# Analog_Input.net
KiCad netlist of a schematic drawn in Altium Designer
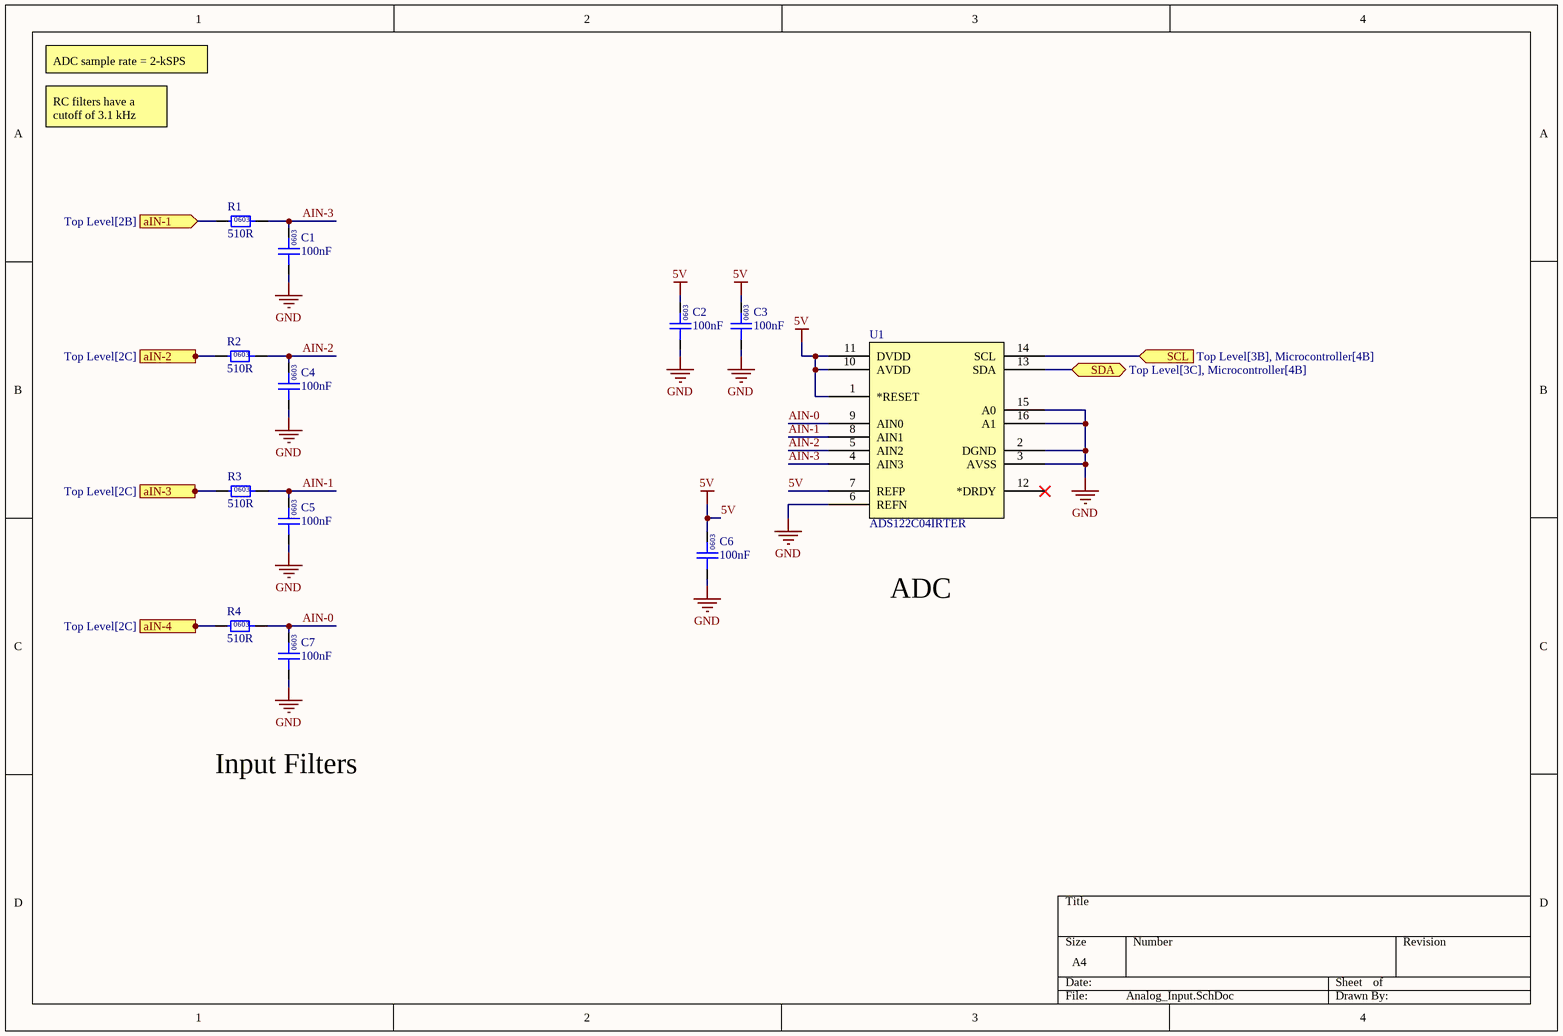
[diagram p0: Analog_Input.SchDoc]

(export (version "E")
  (design (tool "Eeschema 10.0.6"))
  (components
    (comp (ref "C1")
      (value "100nF")
      (footprint "0603")
      (fields
        (field (name "PART NUMBER") "GCM188L81H104KA57D")
        (field (name "MANUFACTURER") "muRata")
        (field (name "TOLERANCE") "±10%")
      )
      (libsource (lib "ts_standard_library") (part "Capacitor 0603"))
    )
    (comp (ref "C2")
      (value "100nF")
      (footprint "0603")
      (fields
        (field (name "PART NUMBER") "GCM188L81H104KA57D")
        (field (name "MANUFACTURER") "muRata")
        (field (name "TOLERANCE") "±10%")
      )
      (libsource (lib "ts_standard_library") (part "Capacitor 0603"))
    )
    (comp (ref "C3")
      (value "100nF")
      (footprint "0603")
      (fields
        (field (name "PART NUMBER") "GCM188L81H104KA57D")
        (field (name "MANUFACTURER") "muRata")
        (field (name "TOLERANCE") "±10%")
      )
      (libsource (lib "ts_standard_library") (part "Capacitor 0603"))
    )
    (comp (ref "C4")
      (value "100nF")
      (footprint "0603")
      (fields
        (field (name "PART NUMBER") "GCM188L81H104KA57D")
        (field (name "MANUFACTURER") "muRata")
        (field (name "TOLERANCE") "±10%")
      )
      (libsource (lib "ts_standard_library") (part "Capacitor 0603"))
    )
    (comp (ref "C5")
      (value "100nF")
      (footprint "0603")
      (fields
        (field (name "PART NUMBER") "GCM188L81H104KA57D")
        (field (name "MANUFACTURER") "muRata")
        (field (name "TOLERANCE") "±10%")
      )
      (libsource (lib "ts_standard_library") (part "Capacitor 0603"))
    )
    (comp (ref "C6")
      (value "100nF")
      (footprint "0603")
      (fields
        (field (name "PART NUMBER") "GCM188L81H104KA57D")
        (field (name "MANUFACTURER") "muRata")
        (field (name "TOLERANCE") "±10%")
      )
      (libsource (lib "ts_standard_library") (part "Capacitor 0603"))
    )
    (comp (ref "C7")
      (value "100nF")
      (footprint "0603")
      (fields
        (field (name "PART NUMBER") "GCM188L81H104KA57D")
        (field (name "MANUFACTURER") "muRata")
        (field (name "TOLERANCE") "±10%")
      )
      (libsource (lib "ts_standard_library") (part "Capacitor 0603"))
    )
    (comp (ref "R1")
      (value "510R")
      (footprint "0603")
      (fields
        (field (name "PART NUMBER") "RC0603FR-07510RL")
        (field (name "MANUFACTURER") "YAGEO")
        (field (name "TOLERANCE") "0.01")
      )
      (libsource (lib "ts_standard_library") (part "Resistor 0603"))
    )
    (comp (ref "R2")
      (value "510R")
      (footprint "0603")
      (fields
        (field (name "PART NUMBER") "RC0603FR-07510RL")
        (field (name "MANUFACTURER") "YAGEO")
        (field (name "TOLERANCE") "0.01")
      )
      (libsource (lib "ts_standard_library") (part "Resistor 0603"))
    )
    (comp (ref "R3")
      (value "510R")
      (footprint "0603")
      (fields
        (field (name "PART NUMBER") "RC0603FR-07510RL")
        (field (name "MANUFACTURER") "YAGEO")
        (field (name "TOLERANCE") "0.01")
      )
      (libsource (lib "ts_standard_library") (part "Resistor 0603"))
    )
    (comp (ref "R4")
      (value "510R")
      (footprint "0603")
      (fields
        (field (name "PART NUMBER") "RC0603FR-07510RL")
        (field (name "MANUFACTURER") "YAGEO")
        (field (name "TOLERANCE") "0.01")
      )
      (libsource (lib "ts_standard_library") (part "Resistor 0603"))
    )
    (comp (ref "U1")
      (value "ADS122C04IRTER")
      (footprint "TI 16-WQFN (3x3)")
      (description "IC ADC 24BIT SIGMA-DELTA 16WQFN")
      (fields
        (field (name "MANUFACTURER") "Texas Instruments")
        (field (name "DIGIKEY PART NUMBER") "296-50886-1-ND")
      )
      (libsource (lib "ts_standard_library") (part "ADS122C04IPW"))
    )
  )
  (nets
    (net (code "1") (name "/AIN-0") (class "Default")
      (node (ref "C7") (pin "2") (pinfunction "2_2") (pintype "passive"))
      (node (ref "R4") (pin "2") (pinfunction "2_2") (pintype "passive"))
      (node (ref "U1") (pin "9") (pinfunction "AIN0_9") (pintype "passive"))
    )
    (net (code "2") (name "/AIN-1") (class "Default")
      (node (ref "C5") (pin "2") (pinfunction "2_2") (pintype "passive"))
      (node (ref "R3") (pin "2") (pinfunction "2_2") (pintype "passive"))
      (node (ref "U1") (pin "8") (pinfunction "AIN1_8") (pintype "passive"))
    )
    (net (code "3") (name "/AIN-2") (class "Default")
      (node (ref "C4") (pin "2") (pinfunction "2_2") (pintype "passive"))
      (node (ref "R2") (pin "2") (pinfunction "2_2") (pintype "passive"))
      (node (ref "U1") (pin "5") (pinfunction "AIN2_5") (pintype "passive"))
    )
    (net (code "4") (name "/AIN-3") (class "Default")
      (node (ref "C1") (pin "2") (pinfunction "2_2") (pintype "passive"))
      (node (ref "R1") (pin "2") (pinfunction "2_2") (pintype "passive"))
      (node (ref "U1") (pin "4") (pinfunction "AIN3_4") (pintype "passive"))
    )
    (net (code "5") (name "/SCL") (class "Default")
      (node (ref "U1") (pin "14") (pinfunction "SCL_14") (pintype "passive"))
    )
    (net (code "6") (name "/SDA") (class "Default")
      (node (ref "U1") (pin "13") (pinfunction "SDA_13") (pintype "passive"))
    )
    (net (code "7") (name "/aIN-1") (class "Default")
      (node (ref "R1") (pin "1") (pinfunction "1_1") (pintype "passive"))
    )
    (net (code "8") (name "/aIN-2") (class "Default")
      (node (ref "R2") (pin "1") (pinfunction "1_1") (pintype "passive"))
    )
    (net (code "9") (name "/aIN-3") (class "Default")
      (node (ref "R3") (pin "1") (pinfunction "1_1") (pintype "passive"))
    )
    (net (code "10") (name "/aIN-4") (class "Default")
      (node (ref "R4") (pin "1") (pinfunction "1_1") (pintype "passive"))
    )
    (net (code "11") (name "5V") (class "Default")
      (node (ref "C2") (pin "2") (pinfunction "2_2") (pintype "passive"))
      (node (ref "C3") (pin "2") (pinfunction "2_2") (pintype "passive"))
      (node (ref "C6") (pin "2") (pinfunction "2_2") (pintype "passive"))
      (node (ref "U1") (pin "1") (pinfunction "*RESET_1") (pintype "passive"))
      (node (ref "U1") (pin "10") (pinfunction "AVDD_10") (pintype "passive"))
      (node (ref "U1") (pin "11") (pinfunction "DVDD_11") (pintype "passive"))
      (node (ref "U1") (pin "7") (pinfunction "REFP_7") (pintype "passive"))
    )
    (net (code "12") (name "GND") (class "Default")
      (node (ref "C1") (pin "1") (pinfunction "1_1") (pintype "passive"))
      (node (ref "C2") (pin "1") (pinfunction "1_1") (pintype "passive"))
      (node (ref "C3") (pin "1") (pinfunction "1_1") (pintype "passive"))
      (node (ref "C4") (pin "1") (pinfunction "1_1") (pintype "passive"))
      (node (ref "C5") (pin "1") (pinfunction "1_1") (pintype "passive"))
      (node (ref "C6") (pin "1") (pinfunction "1_1") (pintype "passive"))
      (node (ref "C7") (pin "1") (pinfunction "1_1") (pintype "passive"))
      (node (ref "U1") (pin "15") (pinfunction "A0_15") (pintype "passive"))
      (node (ref "U1") (pin "16") (pinfunction "A1_16") (pintype "passive"))
      (node (ref "U1") (pin "2") (pinfunction "DGND_2") (pintype "passive"))
      (node (ref "U1") (pin "3") (pinfunction "AVSS_3") (pintype "passive"))
      (node (ref "U1") (pin "6") (pinfunction "REFN_6") (pintype "passive"))
    )
    (net (code "13") (name "unconnected-(U1-*DRDY-Pad12)") (class "Default")
      (node (ref "U1") (pin "12") (pinfunction "*DRDY_12") (pintype "passive+no_connect"))
    )
  )
)
